# SPI_IFC.net
KiCad netlist of a schematic drawn in Altium Designer
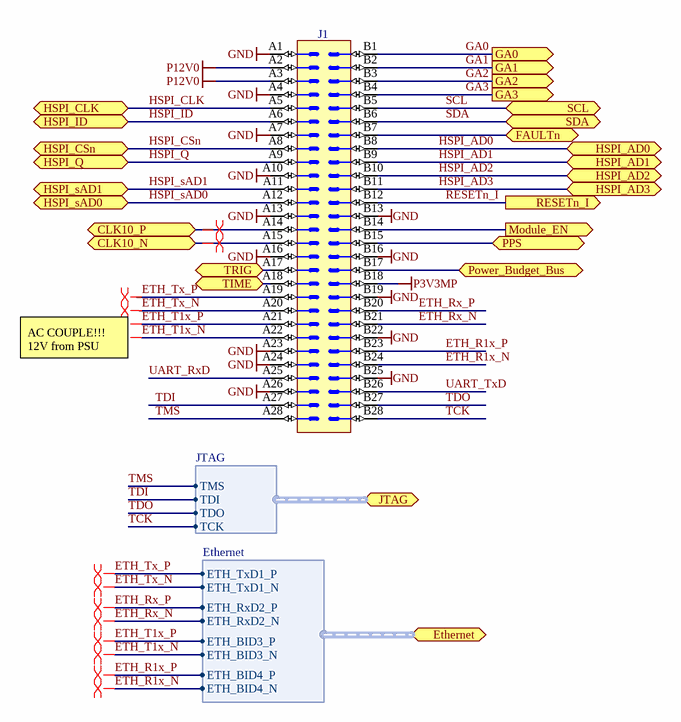
[diagram p0: SPI_IFC.SchDoc]

(export (version "E")
  (design (tool "Eeschema 10.0.6"))
  (components
    (comp (ref "J1")
      (value "~")
      (footprint "AMPHENOL_MINI-COOL-56P")
      (description "64 contacts Board Eddge PCI Express x4 Socket")
      (fields
        (field (name "PART NUMBER") "AMPHENOL_MINI-Cool-56P")
        (field (name "MANUFACTURER") "AMPHENOL")
        (field (name "AUTHOR") "CERN DEM HF")
      )
      (libsource (lib "Connectors") (part "AMPHENOL_MINI-Cool-56P"))
    )
  )
  (nets
    (net (code "3") (name "/CLK10_N") (class "Default")
      (node (ref "J1") (pin "A15") (pinfunction "A15_A15") (pintype "bidirectional"))
    )
    (net (code "4") (name "/CLK10_P") (class "Default")
      (node (ref "J1") (pin "A14") (pinfunction "A14_A14") (pintype "bidirectional"))
    )
    (net (code "5") (name "/ETH_R1x_N") (class "Default")
      (node (ref "J1") (pin "B24") (pinfunction "B24_B24") (pintype "bidirectional"))
    )
    (net (code "6") (name "/ETH_R1x_P") (class "Default")
      (node (ref "J1") (pin "B23") (pinfunction "B23_B23") (pintype "bidirectional"))
    )
    (net (code "7") (name "/ETH_Rx_N") (class "Default")
      (node (ref "J1") (pin "B21") (pinfunction "B21_B21") (pintype "bidirectional"))
    )
    (net (code "8") (name "/ETH_Rx_P") (class "Default")
      (node (ref "J1") (pin "B20") (pinfunction "B20_B20") (pintype "bidirectional"))
    )
    (net (code "9") (name "/ETH_T1x_N") (class "Default")
      (node (ref "J1") (pin "A22") (pinfunction "A22_A22") (pintype "bidirectional"))
    )
    (net (code "10") (name "/ETH_T1x_P") (class "Default")
      (node (ref "J1") (pin "A21") (pinfunction "A21_A21") (pintype "bidirectional"))
    )
    (net (code "11") (name "/ETH_Tx_N") (class "Default")
      (node (ref "J1") (pin "A20") (pinfunction "A20_A20") (pintype "bidirectional"))
    )
    (net (code "12") (name "/ETH_Tx_P") (class "Default")
      (node (ref "J1") (pin "A19") (pinfunction "A19_A19") (pintype "bidirectional"))
    )
    (net (code "13") (name "/FAULTn") (class "Default")
      (node (ref "J1") (pin "B7") (pinfunction "B7_B7") (pintype "bidirectional"))
    )
    (net (code "14") (name "/GA0") (class "Default")
      (node (ref "J1") (pin "B1") (pinfunction "B1_B1") (pintype "bidirectional"))
    )
    (net (code "15") (name "/GA1") (class "Default")
      (node (ref "J1") (pin "B2") (pinfunction "B2_B2") (pintype "bidirectional"))
    )
    (net (code "16") (name "/GA2") (class "Default")
      (node (ref "J1") (pin "B3") (pinfunction "B3_B3") (pintype "bidirectional"))
    )
    (net (code "17") (name "/GA3") (class "Default")
      (node (ref "J1") (pin "B4") (pinfunction "B4_B4") (pintype "bidirectional"))
    )
    (net (code "18") (name "/HSPI_AD0") (class "Default")
      (node (ref "J1") (pin "B8") (pinfunction "B8_B8") (pintype "bidirectional"))
    )
    (net (code "19") (name "/HSPI_AD1") (class "Default")
      (node (ref "J1") (pin "B9") (pinfunction "B9_B9") (pintype "bidirectional"))
    )
    (net (code "20") (name "/HSPI_AD2") (class "Default")
      (node (ref "J1") (pin "B10") (pinfunction "B10_B10") (pintype "bidirectional"))
    )
    (net (code "21") (name "/HSPI_AD3") (class "Default")
      (node (ref "J1") (pin "B11") (pinfunction "B11_B11") (pintype "bidirectional"))
    )
    (net (code "22") (name "/HSPI_CLK") (class "Default")
      (node (ref "J1") (pin "A5") (pinfunction "A5_A5") (pintype "bidirectional"))
    )
    (net (code "23") (name "/HSPI_CSn") (class "Default")
      (node (ref "J1") (pin "A8") (pinfunction "A8_A8") (pintype "bidirectional"))
    )
    (net (code "24") (name "/HSPI_ID") (class "Default")
      (node (ref "J1") (pin "A6") (pinfunction "A6_A6") (pintype "bidirectional"))
    )
    (net (code "25") (name "/HSPI_Q") (class "Default")
      (node (ref "J1") (pin "A9") (pinfunction "A9_A9") (pintype "bidirectional"))
    )
    (net (code "26") (name "/HSPI_sAD0") (class "Default")
      (node (ref "J1") (pin "A12") (pinfunction "A12_A12") (pintype "bidirectional"))
    )
    (net (code "27") (name "/HSPI_sAD1") (class "Default")
      (node (ref "J1") (pin "A11") (pinfunction "A11_A11") (pintype "bidirectional"))
    )
    (net (code "28") (name "/Module_EN") (class "Default")
      (node (ref "J1") (pin "B14") (pinfunction "B14_B14") (pintype "bidirectional"))
    )
    (net (code "29") (name "/PPS") (class "Default")
      (node (ref "J1") (pin "B15") (pinfunction "B15_B15") (pintype "bidirectional"))
    )
    (net (code "30") (name "/Power_Budget_Bus") (class "Default")
      (node (ref "J1") (pin "B17") (pinfunction "B17_B17") (pintype "bidirectional"))
    )
    (net (code "31") (name "/RESETn_I") (class "Default")
      (node (ref "J1") (pin "B12") (pinfunction "B12_B12") (pintype "bidirectional"))
    )
    (net (code "32") (name "/SCL") (class "Default")
      (node (ref "J1") (pin "B5") (pinfunction "B5_B5") (pintype "bidirectional"))
    )
    (net (code "33") (name "/SDA") (class "Default")
      (node (ref "J1") (pin "B6") (pinfunction "B6_B6") (pintype "bidirectional"))
    )
    (net (code "34") (name "/TCK") (class "Default")
      (node (ref "J1") (pin "B28") (pinfunction "B28_B28") (pintype "bidirectional"))
    )
    (net (code "35") (name "/TDI") (class "Default")
      (node (ref "J1") (pin "A27") (pinfunction "A27_A27") (pintype "bidirectional"))
    )
    (net (code "36") (name "/TDO") (class "Default")
      (node (ref "J1") (pin "B27") (pinfunction "B27_B27") (pintype "bidirectional"))
    )
    (net (code "37") (name "/TIME") (class "Default")
      (node (ref "J1") (pin "A18") (pinfunction "A18_A18") (pintype "bidirectional"))
    )
    (net (code "38") (name "/TMS") (class "Default")
      (node (ref "J1") (pin "A28") (pinfunction "A28_A28") (pintype "bidirectional"))
    )
    (net (code "39") (name "/TRIG") (class "Default")
      (node (ref "J1") (pin "A17") (pinfunction "A17_A17") (pintype "bidirectional"))
    )
    (net (code "40") (name "/UART_RxD") (class "Default")
      (node (ref "J1") (pin "A25") (pinfunction "A25_A25") (pintype "bidirectional"))
    )
    (net (code "41") (name "/UART_TxD") (class "Default")
      (node (ref "J1") (pin "B26") (pinfunction "B26_B26") (pintype "bidirectional"))
    )
    (net (code "44") (name "GND") (class "Default")
      (node (ref "J1") (pin "A1") (pinfunction "A1_A1") (pintype "bidirectional"))
      (node (ref "J1") (pin "A10") (pinfunction "A10_A10") (pintype "bidirectional"))
      (node (ref "J1") (pin "A13") (pinfunction "A13_A13") (pintype "bidirectional"))
      (node (ref "J1") (pin "A16") (pinfunction "A16_A16") (pintype "bidirectional"))
      (node (ref "J1") (pin "A23") (pinfunction "A23_A23") (pintype "bidirectional"))
      (node (ref "J1") (pin "A24") (pinfunction "A24_A24") (pintype "bidirectional"))
      (node (ref "J1") (pin "A26") (pinfunction "A26_A26") (pintype "bidirectional"))
      (node (ref "J1") (pin "A4") (pinfunction "A4_A4") (pintype "bidirectional"))
      (node (ref "J1") (pin "A7") (pinfunction "A7_A7") (pintype "bidirectional"))
      (node (ref "J1") (pin "B13") (pinfunction "B13_B13") (pintype "bidirectional"))
      (node (ref "J1") (pin "B16") (pinfunction "B16_B16") (pintype "bidirectional"))
      (node (ref "J1") (pin "B19") (pinfunction "B19_B19") (pintype "bidirectional"))
      (node (ref "J1") (pin "B22") (pinfunction "B22_B22") (pintype "bidirectional"))
      (node (ref "J1") (pin "B25") (pinfunction "B25_B25") (pintype "bidirectional"))
    )
    (net (code "45") (name "P3V3MP") (class "Default")
      (node (ref "J1") (pin "B18") (pinfunction "B18_B18") (pintype "bidirectional"))
    )
    (net (code "46") (name "P12V0") (class "Default")
      (node (ref "J1") (pin "A2") (pinfunction "A2_A2") (pintype "bidirectional"))
      (node (ref "J1") (pin "A3") (pinfunction "A3_A3") (pintype "bidirectional"))
    )
  )
)
